# STM32.net
KiCad netlist of a schematic drawn in Altium Designer
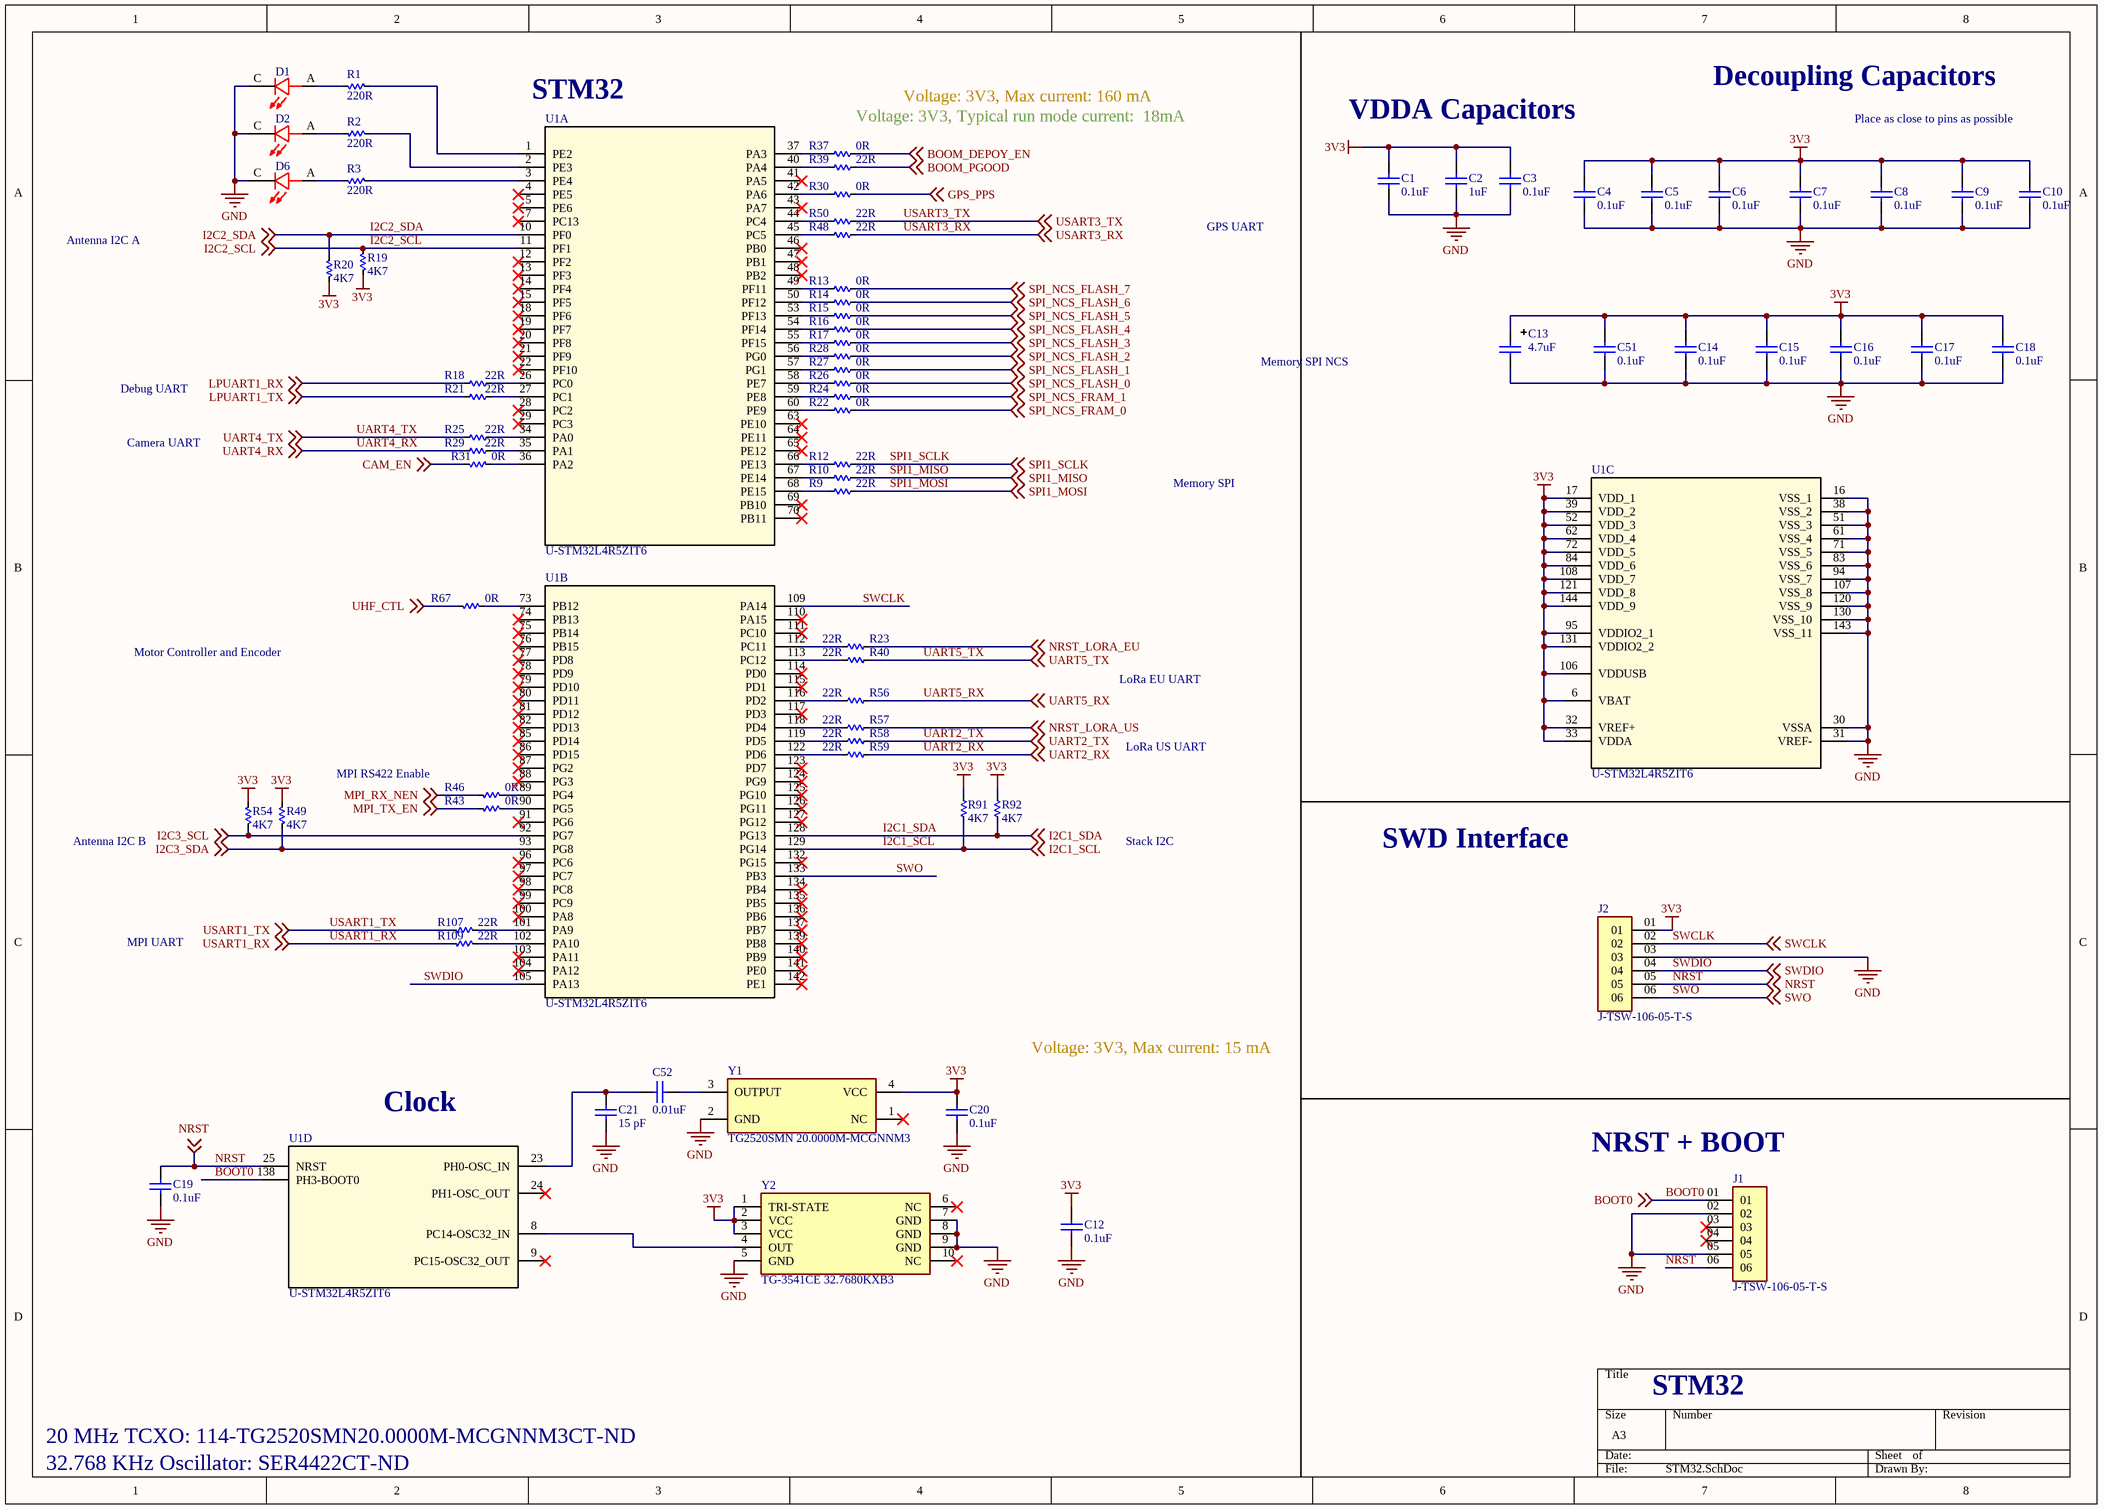
[diagram p0: STM32.SchDoc]

(export (version "E")
  (design (tool "Eeschema 10.0.6"))
  (components
    (comp (ref "C1")
      (value "0.1uF")
      (footprint "0603")
      (description "0.1 µF ±10% 25V Ceramic Capacitor X7R 0603 (1608 Metric)")
      (fields
        (field (name "DISTRIBUTOR PART #") "1276-1006-1-ND")
        (field (name "MANUFACTURER") "Samsung Electro-Mechanics")
      )
      (libsource (lib "OBC Development Board") (part "CC-104-K-25V-X7R-0603"))
    )
    (comp (ref "C2")
      (value "1uF")
      (footprint "0603")
      (description "CAP CER 1UF 25V X7R 0603")
      (fields (field (name "DISTRIBUTOR PART #") "311-1802-1-ND") (field (name "MANUFACTURER") "Yageo"))
      (libsource (lib "OBC Development Board") (part "CC-105-K-25V-X7R-0603"))
    )
    (comp (ref "C3")
      (value "0.1uF")
      (footprint "0603")
      (description "0.1 µF ±10% 25V Ceramic Capacitor X7R 0603 (1608 Metric)")
      (fields
        (field (name "DISTRIBUTOR PART #") "1276-1006-1-ND")
        (field (name "MANUFACTURER") "Samsung Electro-Mechanics")
      )
      (libsource (lib "OBC Development Board") (part "CC-104-K-25V-X7R-0603"))
    )
    (comp (ref "C4")
      (value "0.1uF")
      (footprint "0603")
      (description "0.1 µF ±10% 25V Ceramic Capacitor X7R 0603 (1608 Metric)")
      (fields
        (field (name "DISTRIBUTOR PART #") "1276-1006-1-ND")
        (field (name "MANUFACTURER") "Samsung Electro-Mechanics")
      )
      (libsource (lib "OBC Development Board") (part "CC-104-K-25V-X7R-0603"))
    )
    (comp (ref "C5")
      (value "0.1uF")
      (footprint "0603")
      (description "0.1 µF ±10% 25V Ceramic Capacitor X7R 0603 (1608 Metric)")
      (fields
        (field (name "DISTRIBUTOR PART #") "1276-1006-1-ND")
        (field (name "MANUFACTURER") "Samsung Electro-Mechanics")
      )
      (libsource (lib "OBC Development Board") (part "CC-104-K-25V-X7R-0603"))
    )
    (comp (ref "C6")
      (value "0.1uF")
      (footprint "0603")
      (description "0.1 µF ±10% 25V Ceramic Capacitor X7R 0603 (1608 Metric)")
      (fields
        (field (name "DISTRIBUTOR PART #") "1276-1006-1-ND")
        (field (name "MANUFACTURER") "Samsung Electro-Mechanics")
      )
      (libsource (lib "OBC Development Board") (part "CC-104-K-25V-X7R-0603"))
    )
    (comp (ref "C7")
      (value "0.1uF")
      (footprint "0603")
      (description "0.1 µF ±10% 25V Ceramic Capacitor X7R 0603 (1608 Metric)")
      (fields
        (field (name "DISTRIBUTOR PART #") "1276-1006-1-ND")
        (field (name "MANUFACTURER") "Samsung Electro-Mechanics")
      )
      (libsource (lib "OBC Development Board") (part "CC-104-K-25V-X7R-0603"))
    )
    (comp (ref "C8")
      (value "0.1uF")
      (footprint "0603")
      (description "0.1 µF ±10% 25V Ceramic Capacitor X7R 0603 (1608 Metric)")
      (fields
        (field (name "DISTRIBUTOR PART #") "1276-1006-1-ND")
        (field (name "MANUFACTURER") "Samsung Electro-Mechanics")
      )
      (libsource (lib "OBC Development Board") (part "CC-104-K-25V-X7R-0603"))
    )
    (comp (ref "C9")
      (value "0.1uF")
      (footprint "0603")
      (description "0.1 µF ±10% 25V Ceramic Capacitor X7R 0603 (1608 Metric)")
      (fields
        (field (name "DISTRIBUTOR PART #") "1276-1006-1-ND")
        (field (name "MANUFACTURER") "Samsung Electro-Mechanics")
      )
      (libsource (lib "OBC Development Board") (part "CC-104-K-25V-X7R-0603"))
    )
    (comp (ref "C10")
      (value "0.1uF")
      (footprint "0603")
      (description "0.1 µF ±10% 25V Ceramic Capacitor X7R 0603 (1608 Metric)")
      (fields
        (field (name "DISTRIBUTOR PART #") "1276-1006-1-ND")
        (field (name "MANUFACTURER") "Samsung Electro-Mechanics")
      )
      (libsource (lib "OBC Development Board") (part "CC-104-K-25V-X7R-0603"))
    )
    (comp (ref "C12")
      (value "0.1uF")
      (footprint "0402")
      (description "CAP CER 0.1UF 25V X7R 0402")
      (fields
        (field (name "DISTRIBUTOR PART #") "13-CC0402KPX7R8BB104CT-ND")
        (field (name "MANUFACTURER") "YAGEO")
      )
      (libsource (lib "OBC Development Board") (part "CC-104-K-25V-X7R-0402"))
    )
    (comp (ref "C13")
      (value "4.7uF")
      (footprint "CAP TANT 1206 (A) TCJ")
      (description "4.7 µF Molded Tantalum Capacitors 20 V 1206 (3216 Metric) 4Ohm")
      (fields
        (field (name "DISTRIBUTOR PART #") "478-1668-1-ND")
        (field (name "MANUFACTURER") "AVX Corporation")
      )
      (libsource (lib "OBC Development Board") (part "CT-474-M-20V-OTH-1206"))
    )
    (comp (ref "C14")
      (value "0.1uF")
      (footprint "0603")
      (description "0.1 µF ±10% 25V Ceramic Capacitor X7R 0603 (1608 Metric)")
      (fields
        (field (name "DISTRIBUTOR PART #") "1276-1006-1-ND")
        (field (name "MANUFACTURER") "Samsung Electro-Mechanics")
      )
      (libsource (lib "OBC Development Board") (part "CC-104-K-25V-X7R-0603"))
    )
    (comp (ref "C15")
      (value "0.1uF")
      (footprint "0603")
      (description "0.1 µF ±10% 25V Ceramic Capacitor X7R 0603 (1608 Metric)")
      (fields
        (field (name "DISTRIBUTOR PART #") "1276-1006-1-ND")
        (field (name "MANUFACTURER") "Samsung Electro-Mechanics")
      )
      (libsource (lib "OBC Development Board") (part "CC-104-K-25V-X7R-0603"))
    )
    (comp (ref "C16")
      (value "0.1uF")
      (footprint "0603")
      (description "0.1 µF ±10% 25V Ceramic Capacitor X7R 0603 (1608 Metric)")
      (fields
        (field (name "DISTRIBUTOR PART #") "1276-1006-1-ND")
        (field (name "MANUFACTURER") "Samsung Electro-Mechanics")
      )
      (libsource (lib "OBC Development Board") (part "CC-104-K-25V-X7R-0603"))
    )
    (comp (ref "C17")
      (value "0.1uF")
      (footprint "0603")
      (description "0.1 µF ±10% 25V Ceramic Capacitor X7R 0603 (1608 Metric)")
      (fields
        (field (name "DISTRIBUTOR PART #") "1276-1006-1-ND")
        (field (name "MANUFACTURER") "Samsung Electro-Mechanics")
      )
      (libsource (lib "OBC Development Board") (part "CC-104-K-25V-X7R-0603"))
    )
    (comp (ref "C18")
      (value "0.1uF")
      (footprint "0603")
      (description "0.1 µF ±10% 25V Ceramic Capacitor X7R 0603 (1608 Metric)")
      (fields
        (field (name "DISTRIBUTOR PART #") "1276-1006-1-ND")
        (field (name "MANUFACTURER") "Samsung Electro-Mechanics")
      )
      (libsource (lib "OBC Development Board") (part "CC-104-K-25V-X7R-0603"))
    )
    (comp (ref "C19")
      (value "0.1uF")
      (footprint "0603")
      (description "0.1 µF ±10% 25V Ceramic Capacitor X7R 0603 (1608 Metric)")
      (fields
        (field (name "DISTRIBUTOR PART #") "1276-1006-1-ND")
        (field (name "MANUFACTURER") "Samsung Electro-Mechanics")
      )
      (libsource (lib "OBC Development Board") (part "CC-104-K-25V-X7R-0603"))
    )
    (comp (ref "C20")
      (value "0.1uF")
      (footprint "0402")
      (description "CAP CER 0.1UF 25V X7R 0402")
      (fields
        (field (name "DISTRIBUTOR PART #") "13-CC0402KPX7R8BB104CT-ND")
        (field (name "MANUFACTURER") "YAGEO")
      )
      (libsource (lib "OBC Development Board") (part "CC-104-K-25V-X7R-0402"))
    )
    (comp (ref "C21")
      (value "15 pF")
      (footprint "0402")
      (description "15 pF ±1% 50V Ceramic Capacitor C0G, NP0 0402 (1005 Metric)")
      (fields (field (name "DISTRIBUTOR PART #") "311-1642-1-ND") (field (name "MANUFACTURER") "YAGEO"))
      (libsource (lib "OBC Development Board") (part "CC-159-J-50V-C0G-0402"))
    )
    (comp (ref "C51")
      (value "0.1uF")
      (footprint "0603")
      (description "0.1 µF ±10% 25V Ceramic Capacitor X7R 0603 (1608 Metric)")
      (fields
        (field (name "DISTRIBUTOR PART #") "1276-1006-1-ND")
        (field (name "MANUFACTURER") "Samsung Electro-Mechanics")
      )
      (libsource (lib "OBC Development Board") (part "CC-104-K-25V-X7R-0603"))
    )
    (comp (ref "C52")
      (value "0.01uF")
      (footprint "0603")
      (description "CAP CER 10000PF 50V X7R 0603")
      (fields
        (field (name "DISTRIBUTOR PART #") "1276-1009-1-ND")
        (field (name "MANUFACTURER") "Samsung Electro-Mechanics")
      )
      (libsource (lib "OBC Development Board") (part "CC-105-K-50V-X7R-0603"))
    )
    (comp (ref "D1")
      (value "D-SML-D12U1WT86")
      (footprint "D-SML-D12U1WT86")
      (description "Red 620nm LED Indication - Discrete 2.2V 0603 _1608 Metric")
      (fields
        (field (name "MANUFACTURER PART #") "SML-D12U1WT86")
        (field (name "MANUFACTURER") "Rohm Semiconductor")
      )
      (libsource (lib "OBC Development Board") (part "D-SML-D12U1WT86"))
    )
    (comp (ref "D2")
      (value "D-SML-D12U1WT86")
      (footprint "D-SML-D12U1WT86")
      (description "Red 620nm LED Indication - Discrete 2.2V 0603 _1608 Metric")
      (fields
        (field (name "MANUFACTURER PART #") "SML-D12U1WT86")
        (field (name "MANUFACTURER") "Rohm Semiconductor")
      )
      (libsource (lib "OBC Development Board") (part "D-SML-D12U1WT86"))
    )
    (comp (ref "D6")
      (value "D-SML-D12U1WT86")
      (footprint "D-SML-D12U1WT86")
      (description "Red 620nm LED Indication - Discrete 2.2V 0603 _1608 Metric")
      (fields
        (field (name "MANUFACTURER PART #") "SML-D12U1WT86")
        (field (name "MANUFACTURER") "Rohm Semiconductor")
      )
      (libsource (lib "OBC Development Board") (part "D-SML-D12U1WT86"))
    )
    (comp (ref "J1")
      (value "J-TSW-106-05-T-S")
      (footprint "J-TSW-106-05-T-S")
      (description "CONN HEADER VERT 6POS 2.54MM")
      (fields
        (field (name "DISTRBUTOR PART #") "SAM12323-ND")
        (field (name "MANUFACTURER PART #") "TSW-106-05-T-S")
      )
      (libsource (lib "") (part "J-TSW-106-05-T-S_1"))
    )
    (comp (ref "J2")
      (value "J-TSW-106-05-T-S")
      (footprint "J-TSW-106-05-T-S")
      (description "CONN HEADER VERT 6POS 2.54MM")
      (fields
        (field (name "DISTRBUTOR PART #") "SAM12323-ND")
        (field (name "MANUFACTURER PART #") "TSW-106-05-T-S")
      )
      (libsource (lib "OBC Development Board") (part "J-TSW-106-05-T-S"))
    )
    (comp (ref "R1")
      (value "220R")
      (footprint "0603")
      (description "220 Ohms ±0.5% 0.063W, 1/16W Chip Resistor 0603 (1608 Metric) - Thin Film")
      (fields (field (name "DISTRIBUTOR PART #") "RR08P220DCT-ND") (field (name "MANUFACTURER") "Susumu"))
      (libsource (lib "OBC Development Board") (part "RT-220R-F-1/16W-0603"))
    )
    (comp (ref "R2")
      (value "220R")
      (footprint "0603")
      (description "220 Ohms ±0.5% 0.063W, 1/16W Chip Resistor 0603 (1608 Metric) - Thin Film")
      (fields (field (name "DISTRIBUTOR PART #") "RR08P220DCT-ND") (field (name "MANUFACTURER") "Susumu"))
      (libsource (lib "OBC Development Board") (part "RT-220R-F-1/16W-0603"))
    )
    (comp (ref "R3")
      (value "220R")
      (footprint "0603")
      (description "220 Ohms ±0.5% 0.063W, 1/16W Chip Resistor 0603 (1608 Metric) - Thin Film")
      (fields (field (name "DISTRIBUTOR PART #") "RR08P220DCT-ND") (field (name "MANUFACTURER") "Susumu"))
      (libsource (lib "OBC Development Board") (part "RT-220R-F-1/16W-0603"))
    )
    (comp (ref "R9")
      (value "22R")
      (footprint "0603")
      (description "22 Ohms ±0.5% 0.063W, 1/16W Chip Resistor 0603 (1608 Metric) - Thin Film")
      (fields (field (name "DISTRIBUTOR PART #") "RR08Q22DCT-ND") (field (name "MANUFACTURER") "Susumu"))
      (libsource (lib "OBC Development Board") (part "RT-22R0-F-1/16W-0603"))
    )
    (comp (ref "R10")
      (value "22R")
      (footprint "0603")
      (description "22 Ohms ±0.5% 0.063W, 1/16W Chip Resistor 0603 (1608 Metric) - Thin Film")
      (fields (field (name "DISTRIBUTOR PART #") "RR08Q22DCT-ND") (field (name "MANUFACTURER") "Susumu"))
      (libsource (lib "OBC Development Board") (part "RT-22R0-F-1/16W-0603"))
    )
    (comp (ref "R12")
      (value "22R")
      (footprint "0603")
      (description "22 Ohms ±0.5% 0.063W, 1/16W Chip Resistor 0603 (1608 Metric) - Thin Film")
      (fields (field (name "DISTRIBUTOR PART #") "RR08Q22DCT-ND") (field (name "MANUFACTURER") "Susumu"))
      (libsource (lib "OBC Development Board") (part "RT-22R0-F-1/16W-0603"))
    )
    (comp (ref "R13")
      (value "0R")
      (footprint "0603")
      (description "0 Ohms Jumper 0.1W, 1/10W Chip Resistor 0603 (1608 Metric) Automotive AEC-Q200 Thick Film")
      (fields
        (field (name "DISTRIBUTOR PART #") "RMCF0603ZT0R00CT-ND")
        (field (name "MANUFACTURER") "Stackpole Electronics Inc")
      )
      (libsource (lib "OBC Development Board") (part "RT-0R00-F-1/10W-0603"))
    )
    (comp (ref "R14")
      (value "0R")
      (footprint "0603")
      (description "0 Ohms Jumper 0.1W, 1/10W Chip Resistor 0603 (1608 Metric) Automotive AEC-Q200 Thick Film")
      (fields
        (field (name "DISTRIBUTOR PART #") "RMCF0603ZT0R00CT-ND")
        (field (name "MANUFACTURER") "Stackpole Electronics Inc")
      )
      (libsource (lib "OBC Development Board") (part "RT-0R00-F-1/10W-0603"))
    )
    (comp (ref "R15")
      (value "0R")
      (footprint "0603")
      (description "0 Ohms Jumper 0.1W, 1/10W Chip Resistor 0603 (1608 Metric) Automotive AEC-Q200 Thick Film")
      (fields
        (field (name "DISTRIBUTOR PART #") "RMCF0603ZT0R00CT-ND")
        (field (name "MANUFACTURER") "Stackpole Electronics Inc")
      )
      (libsource (lib "OBC Development Board") (part "RT-0R00-F-1/10W-0603"))
    )
    (comp (ref "R16")
      (value "0R")
      (footprint "0603")
      (description "0 Ohms Jumper 0.1W, 1/10W Chip Resistor 0603 (1608 Metric) Automotive AEC-Q200 Thick Film")
      (fields
        (field (name "DISTRIBUTOR PART #") "RMCF0603ZT0R00CT-ND")
        (field (name "MANUFACTURER") "Stackpole Electronics Inc")
      )
      (libsource (lib "OBC Development Board") (part "RT-0R00-F-1/10W-0603"))
    )
    (comp (ref "R17")
      (value "0R")
      (footprint "0603")
      (description "0 Ohms Jumper 0.1W, 1/10W Chip Resistor 0603 (1608 Metric) Automotive AEC-Q200 Thick Film")
      (fields
        (field (name "DISTRIBUTOR PART #") "RMCF0603ZT0R00CT-ND")
        (field (name "MANUFACTURER") "Stackpole Electronics Inc")
      )
      (libsource (lib "OBC Development Board") (part "RT-0R00-F-1/10W-0603"))
    )
    (comp (ref "R18")
      (value "22R")
      (footprint "0603")
      (description "22 Ohms ±0.5% 0.063W, 1/16W Chip Resistor 0603 (1608 Metric) - Thin Film")
      (fields (field (name "DISTRIBUTOR PART #") "RR08Q22DCT-ND") (field (name "MANUFACTURER") "Susumu"))
      (libsource (lib "OBC Development Board") (part "RT-22R0-F-1/16W-0603"))
    )
    (comp (ref "R19")
      (value "4K7")
      (footprint "0603")
      (description "RES SMD 4.7K OHM 1% 1/10W 0603")
      (fields
        (field (name "DISTRIBUTOR PART #") "CR0603-FX-4701ELFCT-ND")
        (field (name "MANUFACTURER") "Bourns Inc.")
      )
      (libsource (lib "OBC Development Board") (part "RT-4K7-F-1/16W-0603"))
    )
    (comp (ref "R20")
      (value "4K7")
      (footprint "0603")
      (description "RES SMD 4.7K OHM 1% 1/10W 0603")
      (fields
        (field (name "DISTRIBUTOR PART #") "CR0603-FX-4701ELFCT-ND")
        (field (name "MANUFACTURER") "Bourns Inc.")
      )
      (libsource (lib "OBC Development Board") (part "RT-4K7-F-1/16W-0603"))
    )
    (comp (ref "R21")
      (value "22R")
      (footprint "0603")
      (description "22 Ohms ±0.5% 0.063W, 1/16W Chip Resistor 0603 (1608 Metric) - Thin Film")
      (fields (field (name "DISTRIBUTOR PART #") "RR08Q22DCT-ND") (field (name "MANUFACTURER") "Susumu"))
      (libsource (lib "OBC Development Board") (part "RT-22R0-F-1/16W-0603"))
    )
    (comp (ref "R22")
      (value "0R")
      (footprint "0603")
      (description "0 Ohms Jumper 0.1W, 1/10W Chip Resistor 0603 (1608 Metric) Automotive AEC-Q200 Thick Film")
      (fields
        (field (name "DISTRIBUTOR PART #") "RMCF0603ZT0R00CT-ND")
        (field (name "MANUFACTURER") "Stackpole Electronics Inc")
      )
      (libsource (lib "OBC Development Board") (part "RT-0R00-F-1/10W-0603"))
    )
    (comp (ref "R23")
      (value "22R")
      (footprint "0603")
      (description "22 Ohms ±0.5% 0.063W, 1/16W Chip Resistor 0603 (1608 Metric) - Thin Film")
      (fields (field (name "DISTRIBUTOR PART #") "RR08Q22DCT-ND") (field (name "MANUFACTURER") "Susumu"))
      (libsource (lib "OBC Development Board") (part "RT-22R0-F-1/16W-0603"))
    )
    (comp (ref "R24")
      (value "0R")
      (footprint "0603")
      (description "0 Ohms Jumper 0.1W, 1/10W Chip Resistor 0603 (1608 Metric) Automotive AEC-Q200 Thick Film")
      (fields
        (field (name "DISTRIBUTOR PART #") "RMCF0603ZT0R00CT-ND")
        (field (name "MANUFACTURER") "Stackpole Electronics Inc")
      )
      (libsource (lib "OBC Development Board") (part "RT-0R00-F-1/10W-0603"))
    )
    (comp (ref "R25")
      (value "22R")
      (footprint "0603")
      (description "22 Ohms ±0.5% 0.063W, 1/16W Chip Resistor 0603 (1608 Metric) - Thin Film")
      (fields (field (name "DISTRIBUTOR PART #") "RR08Q22DCT-ND") (field (name "MANUFACTURER") "Susumu"))
      (libsource (lib "OBC Development Board") (part "RT-22R0-F-1/16W-0603"))
    )
    (comp (ref "R26")
      (value "0R")
      (footprint "0603")
      (description "0 Ohms Jumper 0.1W, 1/10W Chip Resistor 0603 (1608 Metric) Automotive AEC-Q200 Thick Film")
      (fields
        (field (name "DISTRIBUTOR PART #") "RMCF0603ZT0R00CT-ND")
        (field (name "MANUFACTURER") "Stackpole Electronics Inc")
      )
      (libsource (lib "OBC Development Board") (part "RT-0R00-F-1/10W-0603"))
    )
    (comp (ref "R27")
      (value "0R")
      (footprint "0603")
      (description "0 Ohms Jumper 0.1W, 1/10W Chip Resistor 0603 (1608 Metric) Automotive AEC-Q200 Thick Film")
      (fields
        (field (name "DISTRIBUTOR PART #") "RMCF0603ZT0R00CT-ND")
        (field (name "MANUFACTURER") "Stackpole Electronics Inc")
      )
      (libsource (lib "OBC Development Board") (part "RT-0R00-F-1/10W-0603"))
    )
    (comp (ref "R28")
      (value "0R")
      (footprint "0603")
      (description "0 Ohms Jumper 0.1W, 1/10W Chip Resistor 0603 (1608 Metric) Automotive AEC-Q200 Thick Film")
      (fields
        (field (name "DISTRIBUTOR PART #") "RMCF0603ZT0R00CT-ND")
        (field (name "MANUFACTURER") "Stackpole Electronics Inc")
      )
      (libsource (lib "OBC Development Board") (part "RT-0R00-F-1/10W-0603"))
    )
    (comp (ref "R29")
      (value "22R")
      (footprint "0603")
      (description "22 Ohms ±0.5% 0.063W, 1/16W Chip Resistor 0603 (1608 Metric) - Thin Film")
      (fields (field (name "DISTRIBUTOR PART #") "RR08Q22DCT-ND") (field (name "MANUFACTURER") "Susumu"))
      (libsource (lib "OBC Development Board") (part "RT-22R0-F-1/16W-0603"))
    )
    (comp (ref "R30")
      (value "0R")
      (footprint "0603")
      (description "0 Ohms Jumper 0.1W, 1/10W Chip Resistor 0603 (1608 Metric) Automotive AEC-Q200 Thick Film")
      (fields
        (field (name "DISTRIBUTOR PART #") "RMCF0603ZT0R00CT-ND")
        (field (name "MANUFACTURER") "Stackpole Electronics Inc")
      )
      (libsource (lib "OBC Development Board") (part "RT-0R00-F-1/10W-0603"))
    )
    (comp (ref "R31")
      (value "0R")
      (footprint "0603")
      (description "0 Ohms Jumper 0.1W, 1/10W Chip Resistor 0603 (1608 Metric) Automotive AEC-Q200 Thick Film")
      (fields
        (field (name "DISTRIBUTOR PART #") "RMCF0603ZT0R00CT-ND")
        (field (name "MANUFACTURER") "Stackpole Electronics Inc")
      )
      (libsource (lib "OBC Development Board") (part "RT-0R00-F-1/10W-0603"))
    )
    (comp (ref "R37")
      (value "0R")
      (footprint "0603")
      (description "0 Ohms Jumper 0.1W, 1/10W Chip Resistor 0603 (1608 Metric) Automotive AEC-Q200 Thick Film")
      (fields
        (field (name "DISTRIBUTOR PART #") "RMCF0603ZT0R00CT-ND")
        (field (name "MANUFACTURER") "Stackpole Electronics Inc")
      )
      (libsource (lib "OBC Development Board") (part "RT-0R00-F-1/10W-0603"))
    )
    (comp (ref "R39")
      (value "22R")
      (footprint "0603")
      (description "22 Ohms ±0.5% 0.063W, 1/16W Chip Resistor 0603 (1608 Metric) - Thin Film")
      (fields (field (name "DISTRIBUTOR PART #") "RR08Q22DCT-ND") (field (name "MANUFACTURER") "Susumu"))
      (libsource (lib "OBC Development Board") (part "RT-22R0-F-1/16W-0603"))
    )
    (comp (ref "R40")
      (value "22R")
      (footprint "0603")
      (description "22 Ohms ±0.5% 0.063W, 1/16W Chip Resistor 0603 (1608 Metric) - Thin Film")
      (fields (field (name "DISTRIBUTOR PART #") "RR08Q22DCT-ND") (field (name "MANUFACTURER") "Susumu"))
      (libsource (lib "OBC Development Board") (part "RT-22R0-F-1/16W-0603"))
    )
    (comp (ref "R43")
      (value "0R")
      (footprint "0603")
      (description "0 Ohms Jumper 0.1W, 1/10W Chip Resistor 0603 (1608 Metric) Automotive AEC-Q200 Thick Film")
      (fields
        (field (name "DISTRIBUTOR PART #") "RMCF0603ZT0R00CT-ND")
        (field (name "MANUFACTURER") "Stackpole Electronics Inc")
      )
      (libsource (lib "OBC Development Board") (part "RT-0R00-F-1/10W-0603"))
    )
    (comp (ref "R46")
      (value "0R")
      (footprint "0603")
      (description "0 Ohms Jumper 0.1W, 1/10W Chip Resistor 0603 (1608 Metric) Automotive AEC-Q200 Thick Film")
      (fields
        (field (name "DISTRIBUTOR PART #") "RMCF0603ZT0R00CT-ND")
        (field (name "MANUFACTURER") "Stackpole Electronics Inc")
      )
      (libsource (lib "OBC Development Board") (part "RT-0R00-F-1/10W-0603"))
    )
    (comp (ref "R48")
      (value "22R")
      (footprint "0603")
      (description "22 Ohms ±0.5% 0.063W, 1/16W Chip Resistor 0603 (1608 Metric) - Thin Film")
      (fields (field (name "DISTRIBUTOR PART #") "RR08Q22DCT-ND") (field (name "MANUFACTURER") "Susumu"))
      (libsource (lib "OBC Development Board") (part "RT-22R0-F-1/16W-0603"))
    )
    (comp (ref "R49")
      (value "4K7")
      (footprint "0603")
      (description "RES SMD 4.7K OHM 1% 1/10W 0603")
      (fields
        (field (name "DISTRIBUTOR PART #") "CR0603-FX-4701ELFCT-ND")
        (field (name "MANUFACTURER") "Bourns Inc.")
      )
      (libsource (lib "OBC Development Board") (part "RT-4K7-F-1/16W-0603"))
    )
    (comp (ref "R50")
      (value "22R")
      (footprint "0603")
      (description "22 Ohms ±0.5% 0.063W, 1/16W Chip Resistor 0603 (1608 Metric) - Thin Film")
      (fields (field (name "DISTRIBUTOR PART #") "RR08Q22DCT-ND") (field (name "MANUFACTURER") "Susumu"))
      (libsource (lib "OBC Development Board") (part "RT-22R0-F-1/16W-0603"))
    )
    (comp (ref "R54")
      (value "4K7")
      (footprint "0603")
      (description "RES SMD 4.7K OHM 1% 1/10W 0603")
      (fields
        (field (name "DISTRIBUTOR PART #") "CR0603-FX-4701ELFCT-ND")
        (field (name "MANUFACTURER") "Bourns Inc.")
      )
      (libsource (lib "OBC Development Board") (part "RT-4K7-F-1/16W-0603"))
    )
    (comp (ref "R56")
      (value "22R")
      (footprint "0603")
      (description "22 Ohms ±0.5% 0.063W, 1/16W Chip Resistor 0603 (1608 Metric) - Thin Film")
      (fields (field (name "DISTRIBUTOR PART #") "RR08Q22DCT-ND") (field (name "MANUFACTURER") "Susumu"))
      (libsource (lib "OBC Development Board") (part "RT-22R0-F-1/16W-0603"))
    )
    (comp (ref "R57")
      (value "22R")
      (footprint "0603")
      (description "22 Ohms ±0.5% 0.063W, 1/16W Chip Resistor 0603 (1608 Metric) - Thin Film")
      (fields (field (name "DISTRIBUTOR PART #") "RR08Q22DCT-ND") (field (name "MANUFACTURER") "Susumu"))
      (libsource (lib "OBC Development Board") (part "RT-22R0-F-1/16W-0603"))
    )
    (comp (ref "R58")
      (value "22R")
      (footprint "0603")
      (description "22 Ohms ±0.5% 0.063W, 1/16W Chip Resistor 0603 (1608 Metric) - Thin Film")
      (fields (field (name "DISTRIBUTOR PART #") "RR08Q22DCT-ND") (field (name "MANUFACTURER") "Susumu"))
      (libsource (lib "OBC Development Board") (part "RT-22R0-F-1/16W-0603"))
    )
    (comp (ref "R59")
      (value "22R")
      (footprint "0603")
      (description "22 Ohms ±0.5% 0.063W, 1/16W Chip Resistor 0603 (1608 Metric) - Thin Film")
      (fields (field (name "DISTRIBUTOR PART #") "RR08Q22DCT-ND") (field (name "MANUFACTURER") "Susumu"))
      (libsource (lib "OBC Development Board") (part "RT-22R0-F-1/16W-0603"))
    )
    (comp (ref "R67")
      (value "0R")
      (footprint "0603")
      (description "0 Ohms Jumper 0.1W, 1/10W Chip Resistor 0603 (1608 Metric) Automotive AEC-Q200 Thick Film")
      (fields
        (field (name "DISTRIBUTOR PART #") "RMCF0603ZT0R00CT-ND")
        (field (name "MANUFACTURER") "Stackpole Electronics Inc")
      )
      (libsource (lib "OBC Development Board") (part "RT-0R00-F-1/10W-0603"))
    )
    (comp (ref "R91")
      (value "4K7")
      (footprint "0603")
      (description "RES SMD 4.7K OHM 1% 1/10W 0603")
      (fields
        (field (name "DISTRIBUTOR PART #") "CR0603-FX-4701ELFCT-ND")
        (field (name "MANUFACTURER") "Bourns Inc.")
      )
      (libsource (lib "OBC Development Board") (part "RT-4K7-F-1/16W-0603"))
    )
    (comp (ref "R92")
      (value "4K7")
      (footprint "0603")
      (description "RES SMD 4.7K OHM 1% 1/10W 0603")
      (fields
        (field (name "DISTRIBUTOR PART #") "CR0603-FX-4701ELFCT-ND")
        (field (name "MANUFACTURER") "Bourns Inc.")
      )
      (libsource (lib "OBC Development Board") (part "RT-4K7-F-1/16W-0603"))
    )
    (comp (ref "R107")
      (value "22R")
      (footprint "0603")
      (description "22 Ohms ±0.5% 0.063W, 1/16W Chip Resistor 0603 (1608 Metric) - Thin Film")
      (fields (field (name "DISTRIBUTOR PART #") "RR08Q22DCT-ND") (field (name "MANUFACTURER") "Susumu"))
      (libsource (lib "OBC Development Board") (part "RT-22R0-F-1/16W-0603"))
    )
    (comp (ref "R109")
      (value "22R")
      (footprint "0603")
      (description "22 Ohms ±0.5% 0.063W, 1/16W Chip Resistor 0603 (1608 Metric) - Thin Film")
      (fields (field (name "DISTRIBUTOR PART #") "RR08Q22DCT-ND") (field (name "MANUFACTURER") "Susumu"))
      (libsource (lib "OBC Development Board") (part "RT-22R0-F-1/16W-0603"))
    )
    (comp (ref "U1")
      (value "U-STM32L4R5ZIT6")
      (footprint "U-STM32L4R5ZIT6")
      (description "IC MCU 32BIT 2MB FLASH 144LQFP")
      (fields
        (field (name "MANUFACTURER") "STMicroelectronics")
        (field (name "MANUFACTURER PART #") "STM32L4R5ZIT6")
      )
      (libsource (lib "OBC Development Board") (part "U-STM32L4R5ZIT6"))
    )
    (comp (ref "Y1")
      (value "TG2520SMN 20.0000M-MCGNNM3")
      (footprint "Y-TG2520SMN 20.0000M-MCGNNM3")
      (description "XTAL OSC TCXO 20.0000MHZ CSWV")
      (fields
        (field (name "MANUFACTURER") "EPSON")
        (field (name "DISTRIBUTOR PART #") "114-TG2520SMN20.0000M-MCGNNM3CT-ND")
      )
      (libsource (lib "OBC Development Board") (part "Y-TG2520SMN 20.0000M-MCGNNM3"))
    )
    (comp (ref "Y2")
      (value "TG-3541CE 32.7680KXB3")
      (footprint "Y-TG-3541CE 32.7680KXB3")
      (description "XTAL OSC TCXO 32.7680KHZ CMOS")
      (fields (field (name "MANUFACTURER") "EPSON") (field (name "DISTRIBUTOR PART #") "SER4422CT-ND"))
      (libsource (lib "OBC Development Board") (part "Y-TG-3541CE 32.7680KXB3"))
    )
  )
  (nets
    (net (code "1") (name "3V3") (class "Default")
      (node (ref "C1") (pin "2") (pinfunction "2_2") (pintype "passive"))
      (node (ref "C10") (pin "2") (pinfunction "2_2") (pintype "passive"))
      (node (ref "C12") (pin "2") (pinfunction "2_2") (pintype "passive"))
      (node (ref "C13") (pin "1") (pinfunction "1_1") (pintype "passive"))
      (node (ref "C14") (pin "2") (pinfunction "2_2") (pintype "passive"))
      (node (ref "C15") (pin "2") (pinfunction "2_2") (pintype "passive"))
      (node (ref "C16") (pin "2") (pinfunction "2_2") (pintype "passive"))
      (node (ref "C17") (pin "2") (pinfunction "2_2") (pintype "passive"))
      (node (ref "C18") (pin "2") (pinfunction "2_2") (pintype "passive"))
      (node (ref "C2") (pin "2") (pinfunction "2_2") (pintype "passive"))
      (node (ref "C20") (pin "2") (pinfunction "2_2") (pintype "passive"))
      (node (ref "C3") (pin "2") (pinfunction "2_2") (pintype "passive"))
      (node (ref "C4") (pin "2") (pinfunction "2_2") (pintype "passive"))
      (node (ref "C5") (pin "2") (pinfunction "2_2") (pintype "passive"))
      (node (ref "C51") (pin "2") (pinfunction "2_2") (pintype "passive"))
      (node (ref "C6") (pin "2") (pinfunction "2_2") (pintype "passive"))
      (node (ref "C7") (pin "2") (pinfunction "2_2") (pintype "passive"))
      (node (ref "C8") (pin "2") (pinfunction "2_2") (pintype "passive"))
      (node (ref "C9") (pin "2") (pinfunction "2_2") (pintype "passive"))
      (node (ref "J2") (pin "01") (pinfunction "01_01") (pintype "passive"))
      (node (ref "R19") (pin "1") (pintype "passive"))
      (node (ref "R20") (pin "1") (pintype "passive"))
      (node (ref "R49") (pin "1") (pintype "passive"))
      (node (ref "R54") (pin "1") (pintype "passive"))
      (node (ref "R91") (pin "2") (pintype "passive"))
      (node (ref "R92") (pin "1") (pintype "passive"))
      (node (ref "U1") (pin "106") (pinfunction "VDDUSB_106") (pintype "passive"))
      (node (ref "U1") (pin "108") (pinfunction "VDD_7_108") (pintype "passive"))
      (node (ref "U1") (pin "121") (pinfunction "VDD_8_121") (pintype "passive"))
      (node (ref "U1") (pin "131") (pinfunction "VDDIO2_2_131") (pintype "passive"))
      (node (ref "U1") (pin "144") (pinfunction "VDD_9_144") (pintype "passive"))
      (node (ref "U1") (pin "17") (pinfunction "VDD_1_17") (pintype "passive"))
      (node (ref "U1") (pin "32") (pinfunction "VREF+_32") (pintype "passive"))
      (node (ref "U1") (pin "33") (pinfunction "VDDA_33") (pintype "passive"))
      (node (ref "U1") (pin "39") (pinfunction "VDD_2_39") (pintype "passive"))
      (node (ref "U1") (pin "52") (pinfunction "VDD_3_52") (pintype "passive"))
      (node (ref "U1") (pin "6") (pinfunction "VBAT_6") (pintype "passive"))
      (node (ref "U1") (pin "62") (pinfunction "VDD_4_62") (pintype "passive"))
      (node (ref "U1") (pin "72") (pinfunction "VDD_5_72") (pintype "passive"))
      (node (ref "U1") (pin "84") (pinfunction "VDD_6_84") (pintype "passive"))
      (node (ref "U1") (pin "95") (pinfunction "VDDIO2_1_95") (pintype "passive"))
      (node (ref "Y1") (pin "4") (pinfunction "VCC_4") (pintype "passive"))
      (node (ref "Y2") (pin "1") (pinfunction "TRI-STATE_1") (pintype "passive"))
      (node (ref "Y2") (pin "2") (pinfunction "VCC_2") (pintype "passive"))
      (node (ref "Y2") (pin "3") (pinfunction "VCC_3") (pintype "passive"))
    )
    (net (code "2") (name "BOOM_DEPOY_EN") (class "Default") (node (ref "R37") (pin "2") (pintype "passive")))
    (net (code "3") (name "BOOM_PGOOD") (class "Default") (node (ref "R39") (pin "1") (pintype "passive")))
    (net (code "4") (name "BOOT0") (class "Default")
      (node (ref "J1") (pin "01") (pinfunction "01_01") (pintype "passive"))
      (node (ref "U1") (pin "138") (pinfunction "PH3-BOOT0_138") (pintype "passive"))
    )
    (net (code "5") (name "CAM_EN") (class "Default") (node (ref "R31") (pin "1") (pintype "passive")))
    (net (code "6") (name "GND") (class "Default")
      (node (ref "C1") (pin "1") (pinfunction "1_1") (pintype "passive"))
      (node (ref "C10") (pin "1") (pinfunction "1_1") (pintype "passive"))
      (node (ref "C12") (pin "1") (pinfunction "1_1") (pintype "passive"))
      (node (ref "C13") (pin "2") (pinfunction "2_2") (pintype "passive"))
      (node (ref "C14") (pin "1") (pinfunction "1_1") (pintype "passive"))
      (node (ref "C15") (pin "1") (pinfunction "1_1") (pintype "passive"))
      (node (ref "C16") (pin "1") (pinfunction "1_1") (pintype "passive"))
      (node (ref "C17") (pin "1") (pinfunction "1_1") (pintype "passive"))
      (node (ref "C18") (pin "1") (pinfunction "1_1") (pintype "passive"))
      (node (ref "C19") (pin "1") (pinfunction "1_1") (pintype "passive"))
      (node (ref "C2") (pin "1") (pinfunction "1_1") (pintype "passive"))
      (node (ref "C20") (pin "1") (pinfunction "1_1") (pintype "passive"))
      (node (ref "C21") (pin "2") (pinfunction "2_2") (pintype "passive"))
      (node (ref "C3") (pin "1") (pinfunction "1_1") (pintype "passive"))
      (node (ref "C4") (pin "1") (pinfunction "1_1") (pintype "passive"))
      (node (ref "C5") (pin "1") (pinfunction "1_1") (pintype "passive"))
      (node (ref "C51") (pin "1") (pinfunction "1_1") (pintype "passive"))
      (node (ref "C6") (pin "1") (pinfunction "1_1") (pintype "passive"))
      (node (ref "C7") (pin "1") (pinfunction "1_1") (pintype "passive"))
      (node (ref "C8") (pin "1") (pinfunction "1_1") (pintype "passive"))
      (node (ref "C9") (pin "1") (pinfunction "1_1") (pintype "passive"))
      (node (ref "D1") (pin "C") (pinfunction "C_C") (pintype "passive"))
      (node (ref "D2") (pin "C") (pinfunction "C_C") (pintype "passive"))
      (node (ref "D6") (pin "C") (pinfunction "C_C") (pintype "passive"))
      (node (ref "J1") (pin "02") (pinfunction "02_02") (pintype "passive"))
      (node (ref "J1") (pin "05") (pinfunction "05_05") (pintype "passive"))
      (node (ref "J2") (pin "03") (pinfunction "03_03") (pintype "passive"))
      (node (ref "U1") (pin "107") (pinfunction "VSS_8_107") (pintype "passive"))
      (node (ref "U1") (pin "120") (pinfunction "VSS_9_120") (pintype "passive"))
      (node (ref "U1") (pin "130") (pinfunction "VSS_10_130") (pintype "passive"))
      (node (ref "U1") (pin "143") (pinfunction "VSS_11_143") (pintype "passive"))
      (node (ref "U1") (pin "16") (pinfunction "VSS_1_16") (pintype "passive"))
      (node (ref "U1") (pin "30") (pinfunction "VSSA_30") (pintype "passive"))
      (node (ref "U1") (pin "31") (pinfunction "VREF-_31") (pintype "passive"))
      (node (ref "U1") (pin "38") (pinfunction "VSS_2_38") (pintype "passive"))
      (node (ref "U1") (pin "51") (pinfunction "VSS_3_51") (pintype "passive"))
      (node (ref "U1") (pin "61") (pinfunction "VSS_4_61") (pintype "passive"))
      (node (ref "U1") (pin "71") (pinfunction "VSS_5_71") (pintype "passive"))
      (node (ref "U1") (pin "83") (pinfunction "VSS_6_83") (pintype "passive"))
      (node (ref "U1") (pin "94") (pinfunction "VSS_7_94") (pintype "passive"))
      (node (ref "Y1") (pin "2") (pinfunction "GND_2") (pintype "passive"))
      (node (ref "Y2") (pin "5") (pinfunction "GND_5") (pintype "passive"))
      (node (ref "Y2") (pin "7") (pinfunction "GND_7") (pintype "passive"))
      (node (ref "Y2") (pin "8") (pinfunction "GND_8") (pintype "passive"))
      (node (ref "Y2") (pin "9") (pinfunction "GND_9") (pintype "passive"))
    )
    (net (code "7") (name "GPS_PPS") (class "Default") (node (ref "R30") (pin "2") (pintype "passive")))
    (net (code "8") (name "I2C1_SCL") (class "Default")
      (node (ref "R91") (pin "1") (pintype "passive"))
      (node (ref "U1") (pin "129") (pinfunction "PG14_129") (pintype "passive"))
    )
    (net (code "9") (name "I2C1_SDA") (class "Default")
      (node (ref "R92") (pin "2") (pintype "passive"))
      (node (ref "U1") (pin "128") (pinfunction "PG13_128") (pintype "passive"))
    )
    (net (code "10") (name "I2C2_SCL") (class "Default")
      (node (ref "R19") (pin "2") (pintype "passive"))
      (node (ref "U1") (pin "11") (pinfunction "PF1_11") (pintype "passive"))
    )
    (net (code "11") (name "I2C2_SDA") (class "Default")
      (node (ref "R20") (pin "2") (pintype "passive"))
      (node (ref "U1") (pin "10") (pinfunction "PF0_10") (pintype "passive"))
    )
    (net (code "12") (name "I2C3_SCL") (class "Default")
      (node (ref "R54") (pin "2") (pintype "passive"))
      (node (ref "U1") (pin "92") (pinfunction "PG7_92") (pintype "passive"))
    )
    (net (code "13") (name "I2C3_SDA") (class "Default")
      (node (ref "R49") (pin "2") (pintype "passive"))
      (node (ref "U1") (pin "93") (pinfunction "PG8_93") (pintype "passive"))
    )
    (net (code "14") (name "LPUART1_RX") (class "Default") (node (ref "R18") (pin "1") (pintype "passive")))
    (net (code "15") (name "LPUART1_TX") (class "Default") (node (ref "R21") (pin "1") (pintype "passive")))
    (net (code "16") (name "MPI_RX_NEN") (class "Default") (node (ref "R46") (pin "2") (pintype "passive")))
    (net (code "17") (name "MPI_TX_EN") (class "Default") (node (ref "R43") (pin "2") (pintype "passive")))
    (net (code "18") (name "NRST") (class "Default")
      (node (ref "C19") (pin "2") (pinfunction "2_2") (pintype "passive"))
      (node (ref "J1") (pin "06") (pinfunction "06_06") (pintype "passive"))
      (node (ref "J2") (pin "05") (pinfunction "05_05") (pintype "passive"))
      (node (ref "U1") (pin "25") (pinfunction "NRST_25") (pintype "passive"))
    )
    (net (code "19") (name "NRST_LORA_EU") (class "Default") (node (ref "R23") (pin "2") (pintype "passive")))
    (net (code "20") (name "NRST_LORA_US") (class "Default") (node (ref "R57") (pin "2") (pintype "passive")))
    (net (code "21") (name "Net-(D1-PadA)") (class "Default")
      (node (ref "D1") (pin "A") (pinfunction "A_A") (pintype "passive"))
      (node (ref "R1") (pin "1") (pintype "passive"))
    )
    (net (code "22") (name "Net-(D2-PadA)") (class "Default")
      (node (ref "D2") (pin "A") (pinfunction "A_A") (pintype "passive"))
      (node (ref "R2") (pin "1") (pintype "passive"))
    )
    (net (code "23") (name "Net-(D6-PadA)") (class "Default")
      (node (ref "D6") (pin "A") (pinfunction "A_A") (pintype "passive"))
      (node (ref "R3") (pin "1") (pintype "passive"))
    )
    (net (code "24") (name "Net-(U1A-PA0)") (class "Default")
      (node (ref "R25") (pin "2") (pintype "passive"))
      (node (ref "U1") (pin "34") (pinfunction "PA0_34") (pintype "passive"))
    )
    (net (code "25") (name "Net-(U1A-PA1)") (class "Default")
      (node (ref "R29") (pin "2") (pintype "passive"))
      (node (ref "U1") (pin "35") (pinfunction "PA1_35") (pintype "passive"))
    )
    (net (code "26") (name "Net-(U1A-PA2)") (class "Default")
      (node (ref "R31") (pin "2") (pintype "passive"))
      (node (ref "U1") (pin "36") (pinfunction "PA2_36") (pintype "passive"))
    )
    (net (code "27") (name "Net-(U1A-PA3)") (class "Default")
      (node (ref "R37") (pin "1") (pintype "passive"))
      (node (ref "U1") (pin "37") (pinfunction "PA3_37") (pintype "passive"))
    )
    (net (code "28") (name "Net-(U1A-PA4)") (class "Default")
      (node (ref "R39") (pin "2") (pintype "passive"))
      (node (ref "U1") (pin "40") (pinfunction "PA4_40") (pintype "passive"))
    )
    (net (code "29") (name "Net-(U1A-PA6)") (class "Default")
      (node (ref "R30") (pin "1") (pintype "passive"))
      (node (ref "U1") (pin "42") (pinfunction "PA6_42") (pintype "passive"))
    )
    (net (code "30") (name "Net-(U1A-PC0)") (class "Default")
      (node (ref "R18") (pin "2") (pintype "passive"))
      (node (ref "U1") (pin "26") (pinfunction "PC0_26") (pintype "passive"))
    )
    (net (code "31") (name "Net-(U1A-PC1)") (class "Default")
      (node (ref "R21") (pin "2") (pintype "passive"))
      (node (ref "U1") (pin "27") (pinfunction "PC1_27") (pintype "passive"))
    )
    (net (code "32") (name "Net-(U1A-PC4)") (class "Default")
      (node (ref "R50") (pin "2") (pintype "passive"))
      (node (ref "U1") (pin "44") (pinfunction "PC4_44") (pintype "passive"))
    )
    (net (code "33") (name "Net-(U1A-PC5)") (class "Default")
      (node (ref "R48") (pin "2") (pintype "passive"))
      (node (ref "U1") (pin "45") (pinfunction "PC5_45") (pintype "passive"))
    )
    (net (code "34") (name "Net-(U1A-PE2)") (class "Default")
      (node (ref "R1") (pin "2") (pintype "passive"))
      (node (ref "U1") (pin "1") (pinfunction "PE2_1") (pintype "passive"))
    )
    (net (code "35") (name "Net-(U1A-PE3)") (class "Default")
      (node (ref "R2") (pin "2") (pintype "passive"))
      (node (ref "U1") (pin "2") (pinfunction "PE3_2") (pintype "passive"))
    )
    (net (code "36") (name "Net-(U1A-PE4)") (class "Default")
      (node (ref "R3") (pin "2") (pintype "passive"))
      (node (ref "U1") (pin "3") (pinfunction "PE4_3") (pintype "passive"))
    )
    (net (code "37") (name "Net-(U1A-PE7)") (class "Default")
      (node (ref "R26") (pin "1") (pintype "passive"))
      (node (ref "U1") (pin "58") (pinfunction "PE7_58") (pintype "passive"))
    )
    (net (code "38") (name "Net-(U1A-PE8)") (class "Default")
      (node (ref "R24") (pin "1") (pintype "passive"))
      (node (ref "U1") (pin "59") (pinfunction "PE8_59") (pintype "passive"))
    )
    (net (code "39") (name "Net-(U1A-PE9)") (class "Default")
      (node (ref "R22") (pin "1") (pintype "passive"))
      (node (ref "U1") (pin "60") (pinfunction "PE9_60") (pintype "passive"))
    )
    (net (code "40") (name "Net-(U1A-PE13)") (class "Default")
      (node (ref "R12") (pin "2") (pintype "passive"))
      (node (ref "U1") (pin "66") (pinfunction "PE13_66") (pintype "passive"))
    )
    (net (code "41") (name "Net-(U1A-PE14)") (class "Default")
      (node (ref "R10") (pin "2") (pintype "passive"))
      (node (ref "U1") (pin "67") (pinfunction "PE14_67") (pintype "passive"))
    )
    (net (code "42") (name "Net-(U1A-PE15)") (class "Default")
      (node (ref "R9") (pin "2") (pintype "passive"))
      (node (ref "U1") (pin "68") (pinfunction "PE15_68") (pintype "passive"))
    )
    (net (code "43") (name "Net-(U1A-PF11)") (class "Default")
      (node (ref "R13") (pin "1") (pintype "passive"))
      (node (ref "U1") (pin "49") (pinfunction "PF11_49") (pintype "passive"))
    )
    (net (code "44") (name "Net-(U1A-PF12)") (class "Default")
      (node (ref "R14") (pin "1") (pintype "passive"))
      (node (ref "U1") (pin "50") (pinfunction "PF12_50") (pintype "passive"))
    )
    (net (code "45") (name "Net-(U1A-PF13)") (class "Default")
      (node (ref "R15") (pin "1") (pintype "passive"))
      (node (ref "U1") (pin "53") (pinfunction "PF13_53") (pintype "passive"))
    )
    (net (code "46") (name "Net-(U1A-PF14)") (class "Default")
      (node (ref "R16") (pin "1") (pintype "passive"))
      (node (ref "U1") (pin "54") (pinfunction "PF14_54") (pintype "passive"))
    )
    (net (code "47") (name "Net-(U1A-PF15)") (class "Default")
      (node (ref "R17") (pin "1") (pintype "passive"))
      (node (ref "U1") (pin "55") (pinfunction "PF15_55") (pintype "passive"))
    )
    (net (code "48") (name "Net-(U1A-PG0)") (class "Default")
      (node (ref "R28") (pin "1") (pintype "passive"))
      (node (ref "U1") (pin "56") (pinfunction "PG0_56") (pintype "passive"))
    )
    (net (code "49") (name "Net-(U1A-PG1)") (class "Default")
      (node (ref "R27") (pin "1") (pintype "passive"))
      (node (ref "U1") (pin "57") (pinfunction "PG1_57") (pintype "passive"))
    )
    (net (code "50") (name "Net-(U1B-PA9)") (class "Default")
      (node (ref "R107") (pin "1") (pintype "passive"))
      (node (ref "U1") (pin "101") (pinfunction "PA9_101") (pintype "passive"))
    )
    (net (code "51") (name "Net-(U1B-PA10)") (class "Default")
      (node (ref "R109") (pin "1") (pintype "passive"))
      (node (ref "U1") (pin "102") (pinfunction "PA10_102") (pintype "passive"))
    )
    (net (code "52") (name "Net-(U1B-PB12)") (class "Default")
      (node (ref "R67") (pin "2") (pintype "passive"))
      (node (ref "U1") (pin "73") (pinfunction "PB12_73") (pintype "passive"))
    )
    (net (code "53") (name "Net-(U1B-PC11)") (class "Default")
      (node (ref "R23") (pin "1") (pintype "passive"))
      (node (ref "U1") (pin "112") (pinfunction "PC11_112") (pintype "passive"))
    )
    (net (code "54") (name "Net-(U1B-PC12)") (class "Default")
      (node (ref "R40") (pin "1") (pintype "passive"))
      (node (ref "U1") (pin "113") (pinfunction "PC12_113") (pintype "passive"))
    )
    (net (code "55") (name "Net-(U1B-PD2)") (class "Default")
      (node (ref "R56") (pin "1") (pintype "passive"))
      (node (ref "U1") (pin "116") (pinfunction "PD2_116") (pintype "passive"))
    )
    (net (code "56") (name "Net-(U1B-PD4)") (class "Default")
      (node (ref "R57") (pin "1") (pintype "passive"))
      (node (ref "U1") (pin "118") (pinfunction "PD4_118") (pintype "passive"))
    )
    (net (code "57") (name "Net-(U1B-PD5)") (class "Default")
      (node (ref "R58") (pin "1") (pintype "passive"))
      (node (ref "U1") (pin "119") (pinfunction "PD5_119") (pintype "passive"))
    )
    (net (code "58") (name "Net-(U1B-PD6)") (class "Default")
      (node (ref "R59") (pin "1") (pintype "passive"))
      (node (ref "U1") (pin "122") (pinfunction "PD6_122") (pintype "passive"))
    )
    (net (code "59") (name "Net-(U1B-PG4)") (class "Default")
      (node (ref "R46") (pin "1") (pintype "passive"))
      (node (ref "U1") (pin "89") (pinfunction "PG4_89") (pintype "passive"))
    )
    (net (code "60") (name "Net-(U1B-PG5)") (class "Default")
      (node (ref "R43") (pin "1") (pintype "passive"))
      (node (ref "U1") (pin "90") (pinfunction "PG5_90") (pintype "passive"))
    )
    (net (code "61") (name "Net-(U1D-PC14-OSC32_IN)") (class "Default")
      (node (ref "U1") (pin "8") (pinfunction "PC14-OSC32_IN_8") (pintype "passive"))
      (node (ref "Y2") (pin "4") (pinfunction "OUT_4") (pintype "passive"))
    )
    (net (code "62") (name "Net-(U1D-PH0-OSC_IN)") (class "Default")
      (node (ref "C21") (pin "1") (pinfunction "1_1") (pintype "passive"))
      (node (ref "C52") (pin "1") (pinfunction "1_1") (pintype "passive"))
      (node (ref "U1") (pin "23") (pinfunction "PH0-OSC_IN_23") (pintype "passive"))
    )
    (net (code "63") (name "Net-(Y1-OUTPUT)") (class "Default")
      (node (ref "C52") (pin "2") (pinfunction "2_2") (pintype "passive"))
      (node (ref "Y1") (pin "3") (pinfunction "OUTPUT_3") (pintype "passive"))
    )
    (net (code "64") (name "SPI1_MISO") (class "Default") (node (ref "R10") (pin "1") (pintype "passive")))
    (net (code "65") (name "SPI1_MOSI") (class "Default") (node (ref "R9") (pin "1") (pintype "passive")))
    (net (code "66") (name "SPI1_SCLK") (class "Default") (node (ref "R12") (pin "1") (pintype "passive")))
    (net (code "67") (name "SPI_NCS_FLASH_0") (class "Default")
      (node (ref "R26") (pin "2") (pintype "passive"))
    )
    (net (code "68") (name "SPI_NCS_FLASH_1") (class "Default")
      (node (ref "R27") (pin "2") (pintype "passive"))
    )
    (net (code "69") (name "SPI_NCS_FLASH_2") (class "Default")
      (node (ref "R28") (pin "2") (pintype "passive"))
    )
    (net (code "70") (name "SPI_NCS_FLASH_3") (class "Default")
      (node (ref "R17") (pin "2") (pintype "passive"))
    )
    (net (code "71") (name "SPI_NCS_FLASH_4") (class "Default")
      (node (ref "R16") (pin "2") (pintype "passive"))
    )
    (net (code "72") (name "SPI_NCS_FLASH_5") (class "Default")
      (node (ref "R15") (pin "2") (pintype "passive"))
    )
    (net (code "73") (name "SPI_NCS_FLASH_6") (class "Default")
      (node (ref "R14") (pin "2") (pintype "passive"))
    )
    (net (code "74") (name "SPI_NCS_FLASH_7") (class "Default")
      (node (ref "R13") (pin "2") (pintype "passive"))
    )
    (net (code "75") (name "SPI_NCS_FRAM_0") (class "Default")
      (node (ref "R22") (pin "2") (pintype "passive"))
    )
    (net (code "76") (name "SPI_NCS_FRAM_1") (class "Default")
      (node (ref "R24") (pin "2") (pintype "passive"))
    )
    (net (code "77") (name "SWCLK") (class "Default")
      (node (ref "J2") (pin "02") (pinfunction "02_02") (pintype "passive"))
      (node (ref "U1") (pin "109") (pinfunction "PA14_109") (pintype "passive"))
    )
    (net (code "78") (name "SWDIO") (class "Default")
      (node (ref "J2") (pin "04") (pinfunction "04_04") (pintype "passive"))
      (node (ref "U1") (pin "105") (pinfunction "PA13_105") (pintype "passive"))
    )
    (net (code "79") (name "SWO") (class "Default")
      (node (ref "J2") (pin "06") (pinfunction "06_06") (pintype "passive"))
      (node (ref "U1") (pin "133") (pinfunction "PB3_133") (pintype "passive"))
    )
    (net (code "80") (name "UART2_RX") (class "Default") (node (ref "R59") (pin "2") (pintype "passive")))
    (net (code "81") (name "UART2_TX") (class "Default") (node (ref "R58") (pin "2") (pintype "passive")))
    (net (code "82") (name "UART4_RX") (class "Default") (node (ref "R29") (pin "1") (pintype "passive")))
    (net (code "83") (name "UART4_TX") (class "Default") (node (ref "R25") (pin "1") (pintype "passive")))
    (net (code "84") (name "UART5_RX") (class "Default") (node (ref "R56") (pin "2") (pintype "passive")))
    (net (code "85") (name "UART5_TX") (class "Default") (node (ref "R40") (pin "2") (pintype "passive")))
    (net (code "86") (name "UHF_CTL") (class "Default") (node (ref "R67") (pin "1") (pintype "passive")))
    (net (code "87") (name "USART1_RX") (class "Default") (node (ref "R109") (pin "2") (pintype "passive")))
    (net (code "88") (name "USART1_TX") (class "Default") (node (ref "R107") (pin "2") (pintype "passive")))
    (net (code "89") (name "USART3_RX") (class "Default") (node (ref "R48") (pin "1") (pintype "passive")))
    (net (code "90") (name "USART3_TX") (class "Default") (node (ref "R50") (pin "1") (pintype "passive")))
    (net (code "91") (name "unconnected-(J1-Pad03)") (class "Default")
      (node (ref "J1") (pin "03") (pinfunction "03_03") (pintype "passive+no_connect"))
    )
    (net (code "92") (name "unconnected-(J1-Pad04)") (class "Default")
      (node (ref "J1") (pin "04") (pinfunction "04_04") (pintype "passive+no_connect"))
    )
    (net (code "93") (name "unconnected-(U1A-PA5-Pad41)") (class "Default")
      (node (ref "U1") (pin "41") (pinfunction "PA5_41") (pintype "passive+no_connect"))
    )
    (net (code "94") (name "unconnected-(U1A-PA7-Pad43)") (class "Default")
      (node (ref "U1") (pin "43") (pinfunction "PA7_43") (pintype "passive+no_connect"))
    )
    (net (code "95") (name "unconnected-(U1A-PB0-Pad46)") (class "Default")
      (node (ref "U1") (pin "46") (pinfunction "PB0_46") (pintype "passive+no_connect"))
    )
    (net (code "96") (name "unconnected-(U1A-PB1-Pad47)") (class "Default")
      (node (ref "U1") (pin "47") (pinfunction "PB1_47") (pintype "passive+no_connect"))
    )
    (net (code "97") (name "unconnected-(U1A-PB2-Pad48)") (class "Default")
      (node (ref "U1") (pin "48") (pinfunction "PB2_48") (pintype "passive+no_connect"))
    )
    (net (code "98") (name "unconnected-(U1A-PB10-Pad69)") (class "Default")
      (node (ref "U1") (pin "69") (pinfunction "PB10_69") (pintype "passive+no_connect"))
    )
    (net (code "99") (name "unconnected-(U1A-PB11-Pad70)") (class "Default")
      (node (ref "U1") (pin "70") (pinfunction "PB11_70") (pintype "passive+no_connect"))
    )
    (net (code "100") (name "unconnected-(U1A-PC2-Pad28)") (class "Default")
      (node (ref "U1") (pin "28") (pinfunction "PC2_28") (pintype "passive+no_connect"))
    )
    (net (code "101") (name "unconnected-(U1A-PC3-Pad29)") (class "Default")
      (node (ref "U1") (pin "29") (pinfunction "PC3_29") (pintype "passive+no_connect"))
    )
    (net (code "102") (name "unconnected-(U1A-PC13-Pad7)") (class "Default")
      (node (ref "U1") (pin "7") (pinfunction "PC13_7") (pintype "passive+no_connect"))
    )
    (net (code "103") (name "unconnected-(U1A-PE5-Pad4)") (class "Default")
      (node (ref "U1") (pin "4") (pinfunction "PE5_4") (pintype "passive+no_connect"))
    )
    (net (code "104") (name "unconnected-(U1A-PE6-Pad5)") (class "Default")
      (node (ref "U1") (pin "5") (pinfunction "PE6_5") (pintype "passive+no_connect"))
    )
    (net (code "105") (name "unconnected-(U1A-PE10-Pad63)") (class "Default")
      (node (ref "U1") (pin "63") (pinfunction "PE10_63") (pintype "passive+no_connect"))
    )
    (net (code "106") (name "unconnected-(U1A-PE11-Pad64)") (class "Default")
      (node (ref "U1") (pin "64") (pinfunction "PE11_64") (pintype "passive+no_connect"))
    )
    (net (code "107") (name "unconnected-(U1A-PE12-Pad65)") (class "Default")
      (node (ref "U1") (pin "65") (pinfunction "PE12_65") (pintype "passive+no_connect"))
    )
    (net (code "108") (name "unconnected-(U1A-PF2-Pad12)") (class "Default")
      (node (ref "U1") (pin "12") (pinfunction "PF2_12") (pintype "passive+no_connect"))
    )
    (net (code "109") (name "unconnected-(U1A-PF3-Pad13)") (class "Default")
      (node (ref "U1") (pin "13") (pinfunction "PF3_13") (pintype "passive+no_connect"))
    )
    (net (code "110") (name "unconnected-(U1A-PF4-Pad14)") (class "Default")
      (node (ref "U1") (pin "14") (pinfunction "PF4_14") (pintype "passive+no_connect"))
    )
    (net (code "111") (name "unconnected-(U1A-PF5-Pad15)") (class "Default")
      (node (ref "U1") (pin "15") (pinfunction "PF5_15") (pintype "passive+no_connect"))
    )
    (net (code "112") (name "unconnected-(U1A-PF6-Pad18)") (class "Default")
      (node (ref "U1") (pin "18") (pinfunction "PF6_18") (pintype "passive+no_connect"))
    )
    (net (code "113") (name "unconnected-(U1A-PF7-Pad19)") (class "Default")
      (node (ref "U1") (pin "19") (pinfunction "PF7_19") (pintype "passive+no_connect"))
    )
    (net (code "114") (name "unconnected-(U1A-PF8-Pad20)") (class "Default")
      (node (ref "U1") (pin "20") (pinfunction "PF8_20") (pintype "passive+no_connect"))
    )
    (net (code "115") (name "unconnected-(U1A-PF9-Pad21)") (class "Default")
      (node (ref "U1") (pin "21") (pinfunction "PF9_21") (pintype "passive+no_connect"))
    )
    (net (code "116") (name "unconnected-(U1A-PF10-Pad22)") (class "Default")
      (node (ref "U1") (pin "22") (pinfunction "PF10_22") (pintype "passive+no_connect"))
    )
    (net (code "117") (name "unconnected-(U1B-PA8-Pad100)") (class "Default")
      (node (ref "U1") (pin "100") (pinfunction "PA8_100") (pintype "passive+no_connect"))
    )
    (net (code "118") (name "unconnected-(U1B-PA11-Pad103)") (class "Default")
      (node (ref "U1") (pin "103") (pinfunction "PA11_103") (pintype "passive+no_connect"))
    )
    (net (code "119") (name "unconnected-(U1B-PA12-Pad104)") (class "Default")
      (node (ref "U1") (pin "104") (pinfunction "PA12_104") (pintype "passive+no_connect"))
    )
    (net (code "120") (name "unconnected-(U1B-PA15-Pad110)") (class "Default")
      (node (ref "U1") (pin "110") (pinfunction "PA15_110") (pintype "passive+no_connect"))
    )
    (net (code "121") (name "unconnected-(U1B-PB4-Pad134)") (class "Default")
      (node (ref "U1") (pin "134") (pinfunction "PB4_134") (pintype "passive+no_connect"))
    )
    (net (code "122") (name "unconnected-(U1B-PB5-Pad135)") (class "Default")
      (node (ref "U1") (pin "135") (pinfunction "PB5_135") (pintype "passive+no_connect"))
    )
    (net (code "123") (name "unconnected-(U1B-PB6-Pad136)") (class "Default")
      (node (ref "U1") (pin "136") (pinfunction "PB6_136") (pintype "passive+no_connect"))
    )
    (net (code "124") (name "unconnected-(U1B-PB7-Pad137)") (class "Default")
      (node (ref "U1") (pin "137") (pinfunction "PB7_137") (pintype "passive+no_connect"))
    )
    (net (code "125") (name "unconnected-(U1B-PB8-Pad139)") (class "Default")
      (node (ref "U1") (pin "139") (pinfunction "PB8_139") (pintype "passive+no_connect"))
    )
    (net (code "126") (name "unconnected-(U1B-PB9-Pad140)") (class "Default")
      (node (ref "U1") (pin "140") (pinfunction "PB9_140") (pintype "passive+no_connect"))
    )
    (net (code "127") (name "unconnected-(U1B-PB13-Pad74)") (class "Default")
      (node (ref "U1") (pin "74") (pinfunction "PB13_74") (pintype "passive+no_connect"))
    )
    (net (code "128") (name "unconnected-(U1B-PB14-Pad75)") (class "Default")
      (node (ref "U1") (pin "75") (pinfunction "PB14_75") (pintype "passive+no_connect"))
    )
    (net (code "129") (name "unconnected-(U1B-PB15-Pad76)") (class "Default")
      (node (ref "U1") (pin "76") (pinfunction "PB15_76") (pintype "passive+no_connect"))
    )
    (net (code "130") (name "unconnected-(U1B-PC6-Pad96)") (class "Default")
      (node (ref "U1") (pin "96") (pinfunction "PC6_96") (pintype "passive+no_connect"))
    )
    (net (code "131") (name "unconnected-(U1B-PC7-Pad97)") (class "Default")
      (node (ref "U1") (pin "97") (pinfunction "PC7_97") (pintype "passive+no_connect"))
    )
    (net (code "132") (name "unconnected-(U1B-PC8-Pad98)") (class "Default")
      (node (ref "U1") (pin "98") (pinfunction "PC8_98") (pintype "passive+no_connect"))
    )
    (net (code "133") (name "unconnected-(U1B-PC9-Pad99)") (class "Default")
      (node (ref "U1") (pin "99") (pinfunction "PC9_99") (pintype "passive+no_connect"))
    )
    (net (code "134") (name "unconnected-(U1B-PC10-Pad111)") (class "Default")
      (node (ref "U1") (pin "111") (pinfunction "PC10_111") (pintype "passive+no_connect"))
    )
    (net (code "135") (name "unconnected-(U1B-PD0-Pad114)") (class "Default")
      (node (ref "U1") (pin "114") (pinfunction "PD0_114") (pintype "passive+no_connect"))
    )
    (net (code "136") (name "unconnected-(U1B-PD1-Pad115)") (class "Default")
      (node (ref "U1") (pin "115") (pinfunction "PD1_115") (pintype "passive+no_connect"))
    )
    (net (code "137") (name "unconnected-(U1B-PD3-Pad117)") (class "Default")
      (node (ref "U1") (pin "117") (pinfunction "PD3_117") (pintype "passive+no_connect"))
    )
    (net (code "138") (name "unconnected-(U1B-PD7-Pad123)") (class "Default")
      (node (ref "U1") (pin "123") (pinfunction "PD7_123") (pintype "passive+no_connect"))
    )
    (net (code "139") (name "unconnected-(U1B-PD8-Pad77)") (class "Default")
      (node (ref "U1") (pin "77") (pinfunction "PD8_77") (pintype "passive+no_connect"))
    )
    (net (code "140") (name "unconnected-(U1B-PD9-Pad78)") (class "Default")
      (node (ref "U1") (pin "78") (pinfunction "PD9_78") (pintype "passive+no_connect"))
    )
    (net (code "141") (name "unconnected-(U1B-PD10-Pad79)") (class "Default")
      (node (ref "U1") (pin "79") (pinfunction "PD10_79") (pintype "passive+no_connect"))
    )
    (net (code "142") (name "unconnected-(U1B-PD11-Pad80)") (class "Default")
      (node (ref "U1") (pin "80") (pinfunction "PD11_80") (pintype "passive+no_connect"))
    )
    (net (code "143") (name "unconnected-(U1B-PD12-Pad81)") (class "Default")
      (node (ref "U1") (pin "81") (pinfunction "PD12_81") (pintype "passive+no_connect"))
    )
    (net (code "144") (name "unconnected-(U1B-PD13-Pad82)") (class "Default")
      (node (ref "U1") (pin "82") (pinfunction "PD13_82") (pintype "passive+no_connect"))
    )
    (net (code "145") (name "unconnected-(U1B-PD14-Pad85)") (class "Default")
      (node (ref "U1") (pin "85") (pinfunction "PD14_85") (pintype "passive+no_connect"))
    )
    (net (code "146") (name "unconnected-(U1B-PD15-Pad86)") (class "Default")
      (node (ref "U1") (pin "86") (pinfunction "PD15_86") (pintype "passive+no_connect"))
    )
    (net (code "147") (name "unconnected-(U1B-PE0-Pad141)") (class "Default")
      (node (ref "U1") (pin "141") (pinfunction "PE0_141") (pintype "passive+no_connect"))
    )
    (net (code "148") (name "unconnected-(U1B-PE1-Pad142)") (class "Default")
      (node (ref "U1") (pin "142") (pinfunction "PE1_142") (pintype "passive+no_connect"))
    )
    (net (code "149") (name "unconnected-(U1B-PG2-Pad87)") (class "Default")
      (node (ref "U1") (pin "87") (pinfunction "PG2_87") (pintype "passive+no_connect"))
    )
    (net (code "150") (name "unconnected-(U1B-PG3-Pad88)") (class "Default")
      (node (ref "U1") (pin "88") (pinfunction "PG3_88") (pintype "passive+no_connect"))
    )
    (net (code "151") (name "unconnected-(U1B-PG6-Pad91)") (class "Default")
      (node (ref "U1") (pin "91") (pinfunction "PG6_91") (pintype "passive+no_connect"))
    )
    (net (code "152") (name "unconnected-(U1B-PG9-Pad124)") (class "Default")
      (node (ref "U1") (pin "124") (pinfunction "PG9_124") (pintype "passive+no_connect"))
    )
    (net (code "153") (name "unconnected-(U1B-PG10-Pad125)") (class "Default")
      (node (ref "U1") (pin "125") (pinfunction "PG10_125") (pintype "passive+no_connect"))
    )
    (net (code "154") (name "unconnected-(U1B-PG11-Pad126)") (class "Default")
      (node (ref "U1") (pin "126") (pinfunction "PG11_126") (pintype "passive+no_connect"))
    )
    (net (code "155") (name "unconnected-(U1B-PG12-Pad127)") (class "Default")
      (node (ref "U1") (pin "127") (pinfunction "PG12_127") (pintype "passive+no_connect"))
    )
    (net (code "156") (name "unconnected-(U1B-PG15-Pad132)") (class "Default")
      (node (ref "U1") (pin "132") (pinfunction "PG15_132") (pintype "passive+no_connect"))
    )
    (net (code "157") (name "unconnected-(U1D-PC15-OSC32_OUT-Pad9)") (class "Default")
      (node (ref "U1") (pin "9") (pinfunction "PC15-OSC32_OUT_9") (pintype "passive+no_connect"))
    )
    (net (code "158") (name "unconnected-(U1D-PH1-OSC_OUT-Pad24)") (class "Default")
      (node (ref "U1") (pin "24") (pinfunction "PH1-OSC_OUT_24") (pintype "passive+no_connect"))
    )
    (net (code "159") (name "unconnected-(Y1-NC-Pad1)") (class "Default")
      (node (ref "Y1") (pin "1") (pinfunction "NC_1") (pintype "passive+no_connect"))
    )
    (net (code "160") (name "unconnected-(Y2-NC-Pad6)") (class "Default")
      (node (ref "Y2") (pin "6") (pinfunction "NC_6") (pintype "passive+no_connect"))
    )
    (net (code "161") (name "unconnected-(Y2-NC-Pad10)") (class "Default")
      (node (ref "Y2") (pin "10") (pinfunction "NC_10") (pintype "passive+no_connect"))
    )
  )
)
